# Elekid_02.net
KiCad netlist of a schematic drawn in Altium Designer
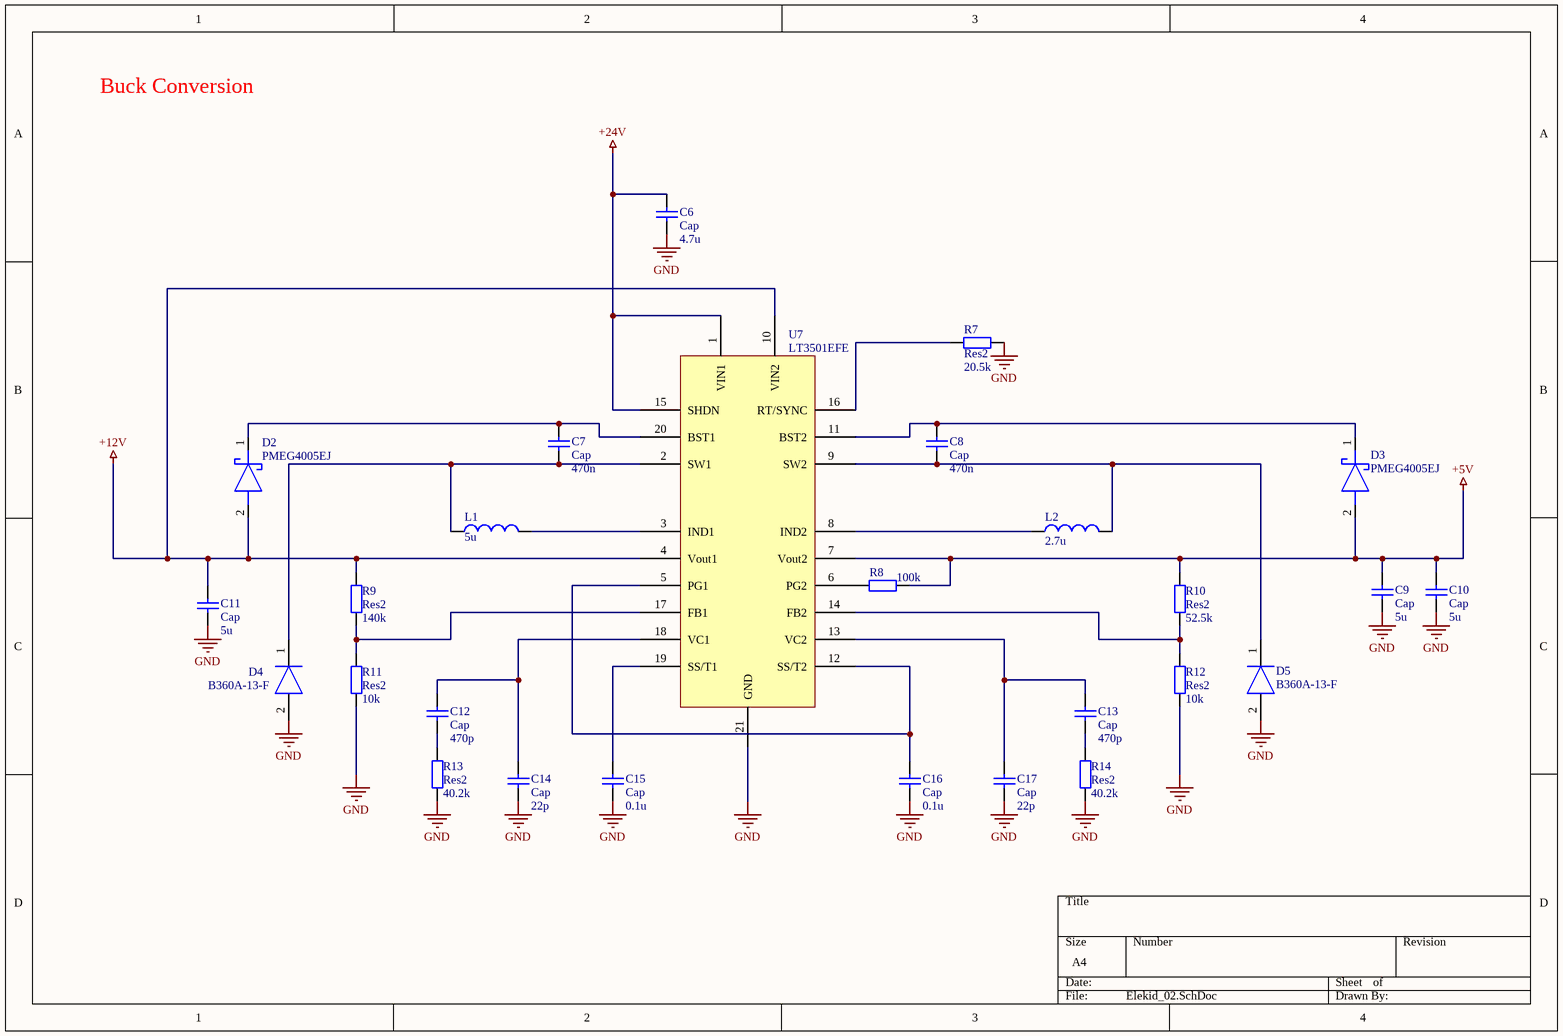
[diagram p0: Elekid_02.SchDoc]

(export (version "E")
  (design (tool "Eeschema 10.0.6"))
  (components
    (comp (ref "C6")
      (value "Cap")
      (footprint "C0805")
      (description "Capacitor")
      (fields (field (name "ALTIUM_VALUE") "4.7u") (field (name "PUBLISHER") "Altium Limited"))
      (libsource (lib "Miscellaneous Devices") (part "Cap"))
    )
    (comp (ref "C7")
      (value "Cap")
      (footprint "C0805")
      (description "Capacitor")
      (fields (field (name "ALTIUM_VALUE") "470n") (field (name "PUBLISHER") "Altium Limited"))
      (libsource (lib "Miscellaneous Devices") (part "Cap"))
    )
    (comp (ref "C8")
      (value "Cap")
      (footprint "C0805")
      (description "Capacitor")
      (fields (field (name "ALTIUM_VALUE") "470n") (field (name "PUBLISHER") "Altium Limited"))
      (libsource (lib "Miscellaneous Devices") (part "Cap"))
    )
    (comp (ref "C9")
      (value "Cap")
      (footprint "C0805")
      (description "Capacitor")
      (fields (field (name "ALTIUM_VALUE") "5u") (field (name "PUBLISHER") "Altium Limited"))
      (libsource (lib "Miscellaneous Devices") (part "Cap"))
    )
    (comp (ref "C10")
      (value "Cap")
      (footprint "C0805")
      (description "Capacitor")
      (fields (field (name "ALTIUM_VALUE") "5u") (field (name "PUBLISHER") "Altium Limited"))
      (libsource (lib "Miscellaneous Devices") (part "Cap"))
    )
    (comp (ref "C11")
      (value "Cap")
      (footprint "C0805")
      (description "Capacitor")
      (fields (field (name "ALTIUM_VALUE") "5u") (field (name "PUBLISHER") "Altium Limited"))
      (libsource (lib "Miscellaneous Devices") (part "Cap"))
    )
    (comp (ref "C12")
      (value "Cap")
      (footprint "C0805")
      (description "Capacitor")
      (fields (field (name "ALTIUM_VALUE") "470p") (field (name "PUBLISHER") "Altium Limited"))
      (libsource (lib "Miscellaneous Devices") (part "Cap"))
    )
    (comp (ref "C13")
      (value "Cap")
      (footprint "C0805")
      (description "Capacitor")
      (fields (field (name "ALTIUM_VALUE") "470p") (field (name "PUBLISHER") "Altium Limited"))
      (libsource (lib "Miscellaneous Devices") (part "Cap"))
    )
    (comp (ref "C14")
      (value "Cap")
      (footprint "C0805")
      (description "Capacitor")
      (fields (field (name "ALTIUM_VALUE") "22p") (field (name "PUBLISHER") "Altium Limited"))
      (libsource (lib "Miscellaneous Devices") (part "Cap"))
    )
    (comp (ref "C15")
      (value "Cap")
      (footprint "C0805")
      (description "Capacitor")
      (fields (field (name "ALTIUM_VALUE") "0.1u") (field (name "PUBLISHER") "Altium Limited"))
      (libsource (lib "Miscellaneous Devices") (part "Cap"))
    )
    (comp (ref "C16")
      (value "Cap")
      (footprint "C0805")
      (description "Capacitor")
      (fields (field (name "ALTIUM_VALUE") "0.1u") (field (name "PUBLISHER") "Altium Limited"))
      (libsource (lib "Miscellaneous Devices") (part "Cap"))
    )
    (comp (ref "C17")
      (value "Cap")
      (footprint "C0805")
      (description "Capacitor")
      (fields (field (name "ALTIUM_VALUE") "22p") (field (name "PUBLISHER") "Altium Limited"))
      (libsource (lib "Miscellaneous Devices") (part "Cap"))
    )
    (comp (ref "D2")
      (value "PMEG4005EJ")
      (footprint "Embedded:SOD2512X80N")
      (description "Schottky Diode")
      (libsource (lib "*") (part "PMEG4005EJ"))
    )
    (comp (ref "D3")
      (value "PMEG4005EJ")
      (footprint "Embedded:SOD2512X80N")
      (description "Schottky Diode")
      (libsource (lib "*") (part "PMEG4005EJ"))
    )
    (comp (ref "D4")
      (value "B360A-13-F")
      (footprint "Embedded:DIOM5226X240N")
      (description "Diode")
      (fields (field (name "MOUSER PART NUMBER") "621-B360A-F"))
      (libsource (lib "*") (part "B360A-13-F"))
    )
    (comp (ref "D5")
      (value "B360A-13-F")
      (footprint "Embedded:DIOM5226X240N")
      (description "Diode")
      (fields (field (name "MOUSER PART NUMBER") "621-B360A-F"))
      (libsource (lib "*") (part "B360A-13-F"))
    )
    (comp (ref "L1")
      (value "5u")
      (footprint "c0805")
      (description "Inductor")
      (fields (field (name "PUBLISHER") "Altium Limited"))
      (libsource (lib "Miscellaneous Devices") (part "Inductor"))
    )
    (comp (ref "L2")
      (value "2.7u")
      (footprint "c0805")
      (description "Inductor")
      (fields (field (name "PUBLISHER") "Altium Limited"))
      (libsource (lib "Miscellaneous Devices") (part "Inductor"))
    )
    (comp (ref "R7")
      (value "Res2")
      (footprint "C0805")
      (description "Resistor")
      (fields (field (name "ALTIUM_VALUE") "20.5k") (field (name "PUBLISHER") "Altium Limited"))
      (libsource (lib "") (part "Res2_2"))
    )
    (comp (ref "R8")
      (value "100k")
      (footprint "C0805")
      (description "Resistor")
      (fields (field (name "Comment") "Res2") (field (name "PUBLISHER") "Altium Limited"))
      (libsource (lib "") (part "Res2_1"))
    )
    (comp (ref "R9")
      (value "Res2")
      (footprint "C0805")
      (description "Resistor")
      (fields (field (name "ALTIUM_VALUE") "140k") (field (name "PUBLISHER") "Altium Limited"))
      (libsource (lib "Miscellaneous Devices") (part "Res2"))
    )
    (comp (ref "R10")
      (value "Res2")
      (footprint "C0805")
      (description "Resistor")
      (fields (field (name "ALTIUM_VALUE") "52.5k") (field (name "PUBLISHER") "Altium Limited"))
      (libsource (lib "Miscellaneous Devices") (part "Res2"))
    )
    (comp (ref "R11")
      (value "Res2")
      (footprint "C0805")
      (description "Resistor")
      (fields (field (name "ALTIUM_VALUE") "10k") (field (name "PUBLISHER") "Altium Limited"))
      (libsource (lib "Miscellaneous Devices") (part "Res2"))
    )
    (comp (ref "R12")
      (value "Res2")
      (footprint "C0805")
      (description "Resistor")
      (fields (field (name "ALTIUM_VALUE") "10k") (field (name "PUBLISHER") "Altium Limited"))
      (libsource (lib "Miscellaneous Devices") (part "Res2"))
    )
    (comp (ref "R13")
      (value "Res2")
      (footprint "C0805")
      (description "Resistor")
      (fields (field (name "ALTIUM_VALUE") "40.2k") (field (name "PUBLISHER") "Altium Limited"))
      (libsource (lib "Miscellaneous Devices") (part "Res2"))
    )
    (comp (ref "R14")
      (value "Res2")
      (footprint "C0805")
      (description "Resistor")
      (fields (field (name "ALTIUM_VALUE") "40.2k") (field (name "PUBLISHER") "Altium Limited"))
      (libsource (lib "Miscellaneous Devices") (part "Res2"))
    )
    (comp (ref "U7")
      (value "LT3501EFE")
      (footprint "SOP65P640X120-21N")
      (libsource (lib "Elekid_Altium_Redo") (part "LT3501EFE"))
    )
  )
  (nets
    (net (code "1") (name "+5V") (class "Default")
      (node (ref "C10") (pin "2") (pinfunction "2_2") (pintype "passive"))
      (node (ref "C9") (pin "2") (pinfunction "2_2") (pintype "passive"))
      (node (ref "D3") (pin "2") (pinfunction "A_2") (pintype "passive"))
      (node (ref "R10") (pin "2") (pinfunction "2_2") (pintype "passive"))
      (node (ref "R8") (pin "1") (pinfunction "1_1") (pintype "passive"))
      (node (ref "U7") (pin "7") (pinfunction "Vout2_7") (pintype "passive"))
    )
    (net (code "2") (name "+12V") (class "Default")
      (node (ref "C11") (pin "2") (pinfunction "2_2") (pintype "passive"))
      (node (ref "D2") (pin "2") (pinfunction "A_2") (pintype "passive"))
      (node (ref "R9") (pin "2") (pinfunction "2_2") (pintype "passive"))
      (node (ref "U7") (pin "10") (pinfunction "VIN2_10") (pintype "passive"))
      (node (ref "U7") (pin "4") (pinfunction "Vout1_4") (pintype "passive"))
    )
    (net (code "3") (name "+24V") (class "Default")
      (node (ref "C6") (pin "2") (pinfunction "2_2") (pintype "passive"))
      (node (ref "U7") (pin "1") (pinfunction "VIN1_1") (pintype "passive"))
      (node (ref "U7") (pin "15") (pinfunction "SHDN_15") (pintype "passive"))
    )
    (net (code "4") (name "GND") (class "Default")
      (node (ref "C10") (pin "1") (pinfunction "1_1") (pintype "passive"))
      (node (ref "C11") (pin "1") (pinfunction "1_1") (pintype "passive"))
      (node (ref "C14") (pin "1") (pinfunction "1_1") (pintype "passive"))
      (node (ref "C15") (pin "1") (pinfunction "1_1") (pintype "passive"))
      (node (ref "C16") (pin "1") (pinfunction "1_1") (pintype "passive"))
      (node (ref "C17") (pin "1") (pinfunction "1_1") (pintype "passive"))
      (node (ref "C6") (pin "1") (pinfunction "1_1") (pintype "passive"))
      (node (ref "C9") (pin "1") (pinfunction "1_1") (pintype "passive"))
      (node (ref "D4") (pin "2") (pinfunction "A_2") (pintype "passive"))
      (node (ref "D5") (pin "2") (pinfunction "A_2") (pintype "passive"))
      (node (ref "R11") (pin "1") (pinfunction "1_1") (pintype "passive"))
      (node (ref "R12") (pin "1") (pinfunction "1_1") (pintype "passive"))
      (node (ref "R13") (pin "1") (pinfunction "1_1") (pintype "passive"))
      (node (ref "R14") (pin "1") (pinfunction "1_1") (pintype "passive"))
      (node (ref "R7") (pin "2") (pinfunction "2_2") (pintype "passive"))
      (node (ref "U7") (pin "21") (pinfunction "GND_21") (pintype "passive"))
    )
    (net (code "5") (name "Net-(C12-Pad1)") (class "Default")
      (node (ref "C12") (pin "1") (pinfunction "1_1") (pintype "passive"))
      (node (ref "R13") (pin "2") (pinfunction "2_2") (pintype "passive"))
    )
    (net (code "6") (name "Net-(C13-Pad1)") (class "Default")
      (node (ref "C13") (pin "1") (pinfunction "1_1") (pintype "passive"))
      (node (ref "R14") (pin "2") (pinfunction "2_2") (pintype "passive"))
    )
    (net (code "7") (name "Net-(D2-K)") (class "Default")
      (node (ref "C7") (pin "2") (pinfunction "2_2") (pintype "passive"))
      (node (ref "D2") (pin "1") (pinfunction "K_1") (pintype "passive"))
      (node (ref "U7") (pin "20") (pinfunction "BST1_20") (pintype "passive"))
    )
    (net (code "8") (name "Net-(D3-K)") (class "Default")
      (node (ref "C8") (pin "2") (pinfunction "2_2") (pintype "passive"))
      (node (ref "D3") (pin "1") (pinfunction "K_1") (pintype "passive"))
      (node (ref "U7") (pin "11") (pinfunction "BST2_11") (pintype "passive"))
    )
    (net (code "9") (name "Net-(D4-K)") (class "Default")
      (node (ref "C7") (pin "1") (pinfunction "1_1") (pintype "passive"))
      (node (ref "D4") (pin "1") (pinfunction "K_1") (pintype "passive"))
      (node (ref "L1") (pin "1") (pinfunction "1_1") (pintype "passive"))
      (node (ref "U7") (pin "2") (pinfunction "SW1_2") (pintype "passive"))
    )
    (net (code "10") (name "Net-(D5-K)") (class "Default")
      (node (ref "C8") (pin "1") (pinfunction "1_1") (pintype "passive"))
      (node (ref "D5") (pin "1") (pinfunction "K_1") (pintype "passive"))
      (node (ref "L2") (pin "2") (pinfunction "2_2") (pintype "passive"))
      (node (ref "U7") (pin "9") (pinfunction "SW2_9") (pintype "passive"))
    )
    (net (code "11") (name "Net-(U7-FB1)") (class "Default")
      (node (ref "R11") (pin "2") (pinfunction "2_2") (pintype "passive"))
      (node (ref "R9") (pin "1") (pinfunction "1_1") (pintype "passive"))
      (node (ref "U7") (pin "17") (pinfunction "FB1_17") (pintype "passive"))
    )
    (net (code "12") (name "Net-(U7-FB2)") (class "Default")
      (node (ref "R10") (pin "1") (pinfunction "1_1") (pintype "passive"))
      (node (ref "R12") (pin "2") (pinfunction "2_2") (pintype "passive"))
      (node (ref "U7") (pin "14") (pinfunction "FB2_14") (pintype "passive"))
    )
    (net (code "13") (name "Net-(U7-IND1)") (class "Default")
      (node (ref "L1") (pin "2") (pinfunction "2_2") (pintype "passive"))
      (node (ref "U7") (pin "3") (pinfunction "IND1_3") (pintype "passive"))
    )
    (net (code "14") (name "Net-(U7-IND2)") (class "Default")
      (node (ref "L2") (pin "1") (pinfunction "1_1") (pintype "passive"))
      (node (ref "U7") (pin "8") (pinfunction "IND2_8") (pintype "passive"))
    )
    (net (code "15") (name "Net-(U7-PG1)") (class "Default")
      (node (ref "C16") (pin "2") (pinfunction "2_2") (pintype "passive"))
      (node (ref "U7") (pin "12") (pinfunction "SS/T2_12") (pintype "passive"))
      (node (ref "U7") (pin "5") (pinfunction "PG1_5") (pintype "passive"))
    )
    (net (code "16") (name "Net-(U7-PG2)") (class "Default")
      (node (ref "R8") (pin "2") (pinfunction "2_2") (pintype "passive"))
      (node (ref "U7") (pin "6") (pinfunction "PG2_6") (pintype "passive"))
    )
    (net (code "17") (name "Net-(U7-RT{slash}SYNC)") (class "Default")
      (node (ref "R7") (pin "1") (pinfunction "1_1") (pintype "passive"))
      (node (ref "U7") (pin "16") (pinfunction "RT/SYNC_16") (pintype "passive"))
    )
    (net (code "18") (name "Net-(U7-SS{slash}T1)") (class "Default")
      (node (ref "C15") (pin "2") (pinfunction "2_2") (pintype "passive"))
      (node (ref "U7") (pin "19") (pinfunction "SS/T1_19") (pintype "passive"))
    )
    (net (code "19") (name "Net-(U7-VC1)") (class "Default")
      (node (ref "C12") (pin "2") (pinfunction "2_2") (pintype "passive"))
      (node (ref "C14") (pin "2") (pinfunction "2_2") (pintype "passive"))
      (node (ref "U7") (pin "18") (pinfunction "VC1_18") (pintype "passive"))
    )
    (net (code "20") (name "Net-(U7-VC2)") (class "Default")
      (node (ref "C13") (pin "2") (pinfunction "2_2") (pintype "passive"))
      (node (ref "C17") (pin "2") (pinfunction "2_2") (pintype "passive"))
      (node (ref "U7") (pin "13") (pinfunction "VC2_13") (pintype "passive"))
    )
  )
)
